# Wifi.net
KiCad netlist of a schematic drawn in Altium Designer
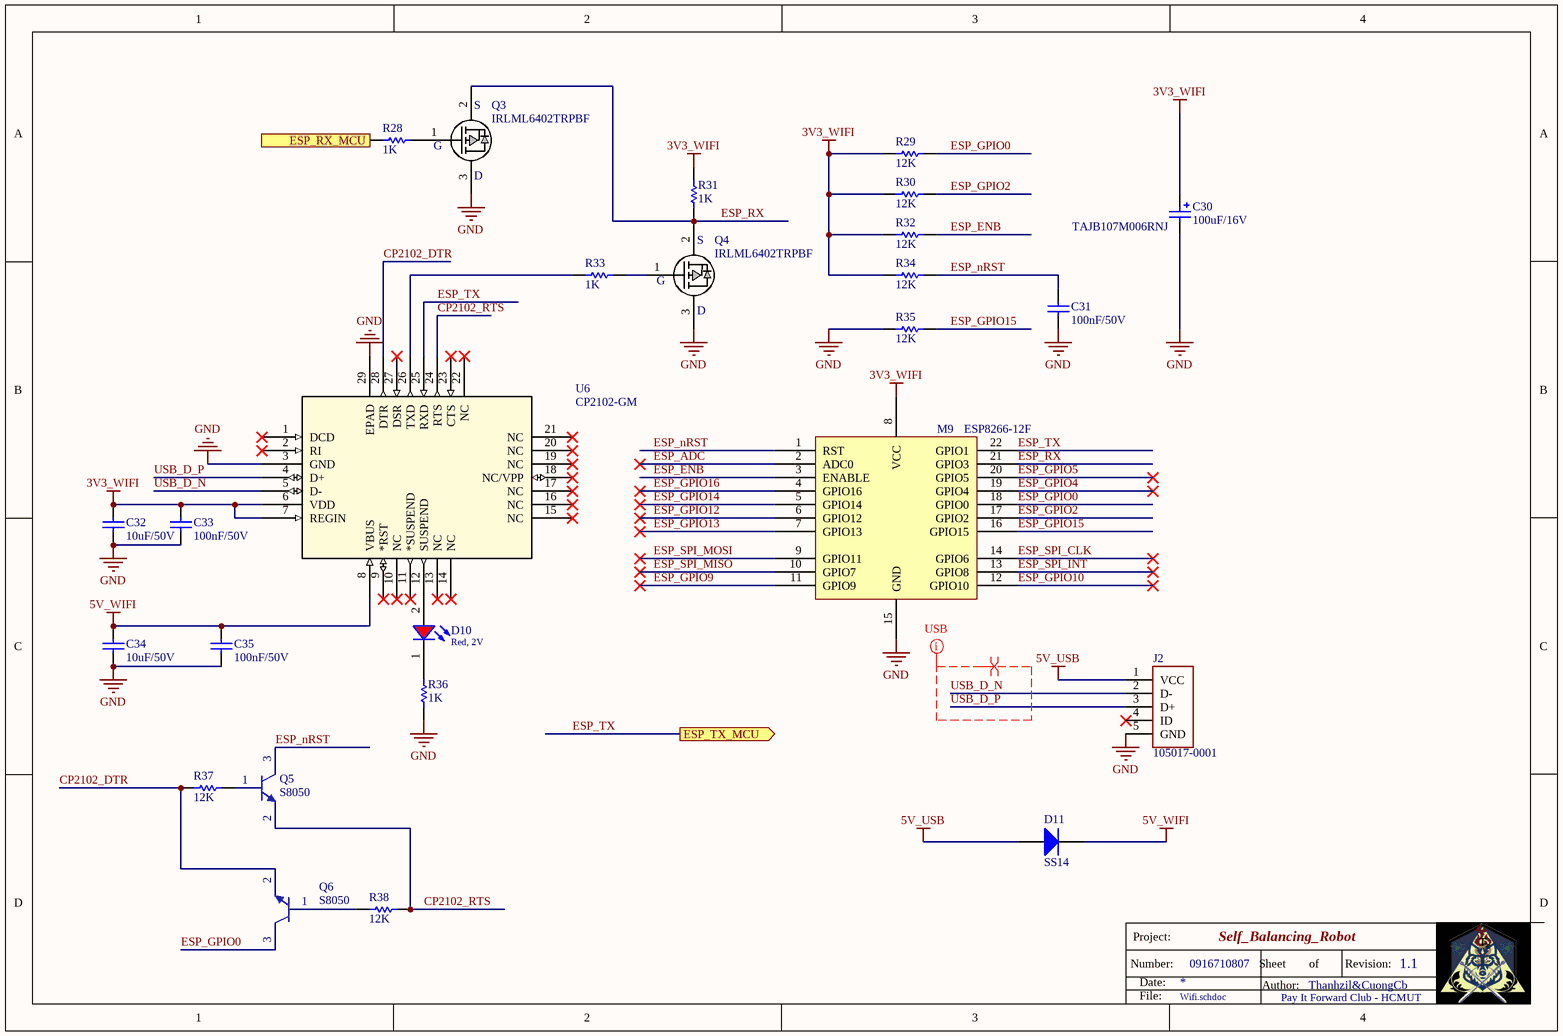
[diagram p0: Wifi.SchDoc]

(export (version "E")
  (design (tool "Eeschema 10.0.6"))
  (components
    (comp (ref "C30")
      (value "100uF/16V")
      (footprint "CAP_SM_TAN")
      (fields
        (field (name "MANUFACTURER") "Nichicon")
        (field (name "MANUFACTURER PART NUMBER") "UWX1C101MCL1GB")
        (field (name "Comment") "TAJB107M006RNJ")
      )
      (libsource (lib "Capacitor") (part "Cap-Tan-100uF-16V"))
    )
    (comp (ref "C31")
      (value "100nF/50V")
      (footprint "CAP-SM-0805")
      (description "CAP CER 0.1UF 50V Y5V 0805")
      (fields
        (field (name "MANUFACTURER") "Samsung Electro-Mechanics")
        (field (name "MANUFACTURER PART NUMBER") "CL21F104ZBCNNNC")
      )
      (libsource (lib "Capacitor") (part "Cap-100nF-50V-0805"))
    )
    (comp (ref "C32")
      (value "10uF/50V")
      (footprint "CAP-SM-0805")
      (description "CAP CER 10UF 50V X5R 0805")
      (fields
        (field (name "MANUFACTURER") "Yageo")
        (field (name "MANUFACTURER PART NUMBER") "CC0805KKX5R9BB106")
      )
      (libsource (lib "Capacitor") (part "Cap-10uF-50V-0805"))
    )
    (comp (ref "C33")
      (value "100nF/50V")
      (footprint "CAP-SM-0805")
      (description "CAP CER 0.1UF 50V Y5V 0805")
      (fields
        (field (name "MANUFACTURER") "Samsung Electro-Mechanics")
        (field (name "MANUFACTURER PART NUMBER") "CL21F104ZBCNNNC")
      )
      (libsource (lib "Capacitor") (part "Cap-100nF-50V-0805"))
    )
    (comp (ref "C34")
      (value "10uF/50V")
      (footprint "CAP-SM-0805")
      (description "CAP CER 10UF 50V X5R 0805")
      (fields
        (field (name "MANUFACTURER") "Yageo")
        (field (name "MANUFACTURER PART NUMBER") "CC0805KKX5R9BB106")
      )
      (libsource (lib "Capacitor") (part "Cap-10uF-50V-0805"))
    )
    (comp (ref "C35")
      (value "100nF/50V")
      (footprint "CAP-SM-0805")
      (description "CAP CER 0.1UF 50V Y5V 0805")
      (fields
        (field (name "MANUFACTURER") "Samsung Electro-Mechanics")
        (field (name "MANUFACTURER PART NUMBER") "CL21F104ZBCNNNC")
      )
      (libsource (lib "Capacitor") (part "Cap-100nF-50V-0805"))
    )
    (comp (ref "D10")
      (value "Red, 2V")
      (footprint "WL-SMCW_0805")
      (description "WL-SMCW SMT Mono-color Chip LED Waterclear, size 0805, Red, 2V, 140deg")
      (fields (field (name "PART NUMBER") "150080RS75000") (field (name "PUBLISHER") "Wurth Elektronik"))
      (libsource (lib "LED_150060BS75000_Altium_WL-SMCW_rev20a") (part "150080RS75000"))
    )
    (comp (ref "D11")
      (value "SS14")
      (footprint "SS14")
      (description "DIODE SCHOTTKY 40V 1A SMA")
      (fields (field (name "MANUFACTURER") "ON Semiconductor"))
      (libsource (lib "Diode") (part "Diode-SS14"))
    )
    (comp (ref "J2")
      (value "105017-0001")
      (footprint "CONN_105017-0001")
      (description "No Description Available")
      (fields (field (name "COPYRIGHT") "Copyright (C) 2018 Accelerated Designs. All rights reserved"))
      (libsource (lib "Header-connector") (part "105017-0001"))
    )
    (comp (ref "M9")
      (value "ESP8266-12F")
      (footprint "ESP8266-12F")
      (fields (field (name "LOCAL SUPPLIER LINK PART NUMBER") "HS000912"))
      (libsource (lib "PIFWRoBot") (part "ESP8266-12F"))
    )
    (comp (ref "Q3")
      (value "IRLML6402TRPBF")
      (footprint "SOT23_NEX")
      (description "P-Channel 20V 3.7A (Ta) 1.3W (Ta) Surface Mount Micro3™/SOT-23")
      (libsource (lib "MOSFET") (part "IRLML6402TRPBF"))
    )
    (comp (ref "Q4")
      (value "IRLML6402TRPBF")
      (footprint "SOT23_NEX")
      (description "P-Channel 20V 3.7A (Ta) 1.3W (Ta) Surface Mount Micro3™/SOT-23")
      (libsource (lib "MOSFET") (part "IRLML6402TRPBF"))
    )
    (comp (ref "Q5") (value "S8050") (footprint "SOT23_NEX") (libsource (lib "BJT") (part "S8050")))
    (comp (ref "Q6") (value "S8050") (footprint "SOT23_NEX") (libsource (lib "BJT") (part "S8050")))
    (comp (ref "R28")
      (value "1K")
      (footprint "Resistor:RES-SM-0805")
      (description "RES 1K OHM 1% 1/4W 0805")
      (fields
        (field (name "MANUFACTURER") "Stackpole Electronics Inc")
        (field (name "MANUFACTURER PART NUMBER") "RNCP0805FTD1K00")
      )
      (libsource (lib "Resistor") (part "Res-1K-0805"))
    )
    (comp (ref "R29")
      (value "12K")
      (footprint "Resistor:RES-SM-0805")
      (description "RES 12 KOHM JUMPER 0805")
      (fields
        (field (name "MANUFACTURER") "Vishay Thin Film")
        (field (name "MANUFACTURER PART NUMBER") "PAT0805E3121BST1")
      )
      (libsource (lib "Resistor") (part "Res-12K-0805"))
    )
    (comp (ref "R30")
      (value "12K")
      (footprint "Resistor:RES-SM-0805")
      (description "RES 12 KOHM JUMPER 0805")
      (fields
        (field (name "MANUFACTURER") "Vishay Thin Film")
        (field (name "MANUFACTURER PART NUMBER") "PAT0805E3121BST1")
      )
      (libsource (lib "Resistor") (part "Res-12K-0805"))
    )
    (comp (ref "R31")
      (value "1K")
      (footprint "Resistor:RES-SM-0805")
      (description "RES 1K OHM 1% 1/4W 0805")
      (fields
        (field (name "MANUFACTURER") "Stackpole Electronics Inc")
        (field (name "MANUFACTURER PART NUMBER") "RNCP0805FTD1K00")
      )
      (libsource (lib "Resistor") (part "Res-1K-0805"))
    )
    (comp (ref "R32")
      (value "12K")
      (footprint "Resistor:RES-SM-0805")
      (description "RES 12 KOHM JUMPER 0805")
      (fields
        (field (name "MANUFACTURER") "Vishay Thin Film")
        (field (name "MANUFACTURER PART NUMBER") "PAT0805E3121BST1")
      )
      (libsource (lib "Resistor") (part "Res-12K-0805"))
    )
    (comp (ref "R33")
      (value "1K")
      (footprint "Resistor:RES-SM-0805")
      (description "RES 1K OHM 1% 1/4W 0805")
      (fields
        (field (name "MANUFACTURER") "Stackpole Electronics Inc")
        (field (name "MANUFACTURER PART NUMBER") "RNCP0805FTD1K00")
      )
      (libsource (lib "Resistor") (part "Res-1K-0805"))
    )
    (comp (ref "R34")
      (value "12K")
      (footprint "Resistor:RES-SM-0805")
      (description "RES 12 KOHM JUMPER 0805")
      (fields
        (field (name "MANUFACTURER") "Vishay Thin Film")
        (field (name "MANUFACTURER PART NUMBER") "PAT0805E3121BST1")
      )
      (libsource (lib "Resistor") (part "Res-12K-0805"))
    )
    (comp (ref "R35")
      (value "12K")
      (footprint "Resistor:RES-SM-0805")
      (description "RES 12 KOHM JUMPER 0805")
      (fields
        (field (name "MANUFACTURER") "Vishay Thin Film")
        (field (name "MANUFACTURER PART NUMBER") "PAT0805E3121BST1")
      )
      (libsource (lib "Resistor") (part "Res-12K-0805"))
    )
    (comp (ref "R36")
      (value "1K")
      (footprint "Resistor:RES-SM-0805")
      (description "RES 1K OHM 1% 1/4W 0805")
      (fields
        (field (name "MANUFACTURER") "Stackpole Electronics Inc")
        (field (name "MANUFACTURER PART NUMBER") "RNCP0805FTD1K00")
      )
      (libsource (lib "Resistor") (part "Res-1K-0805"))
    )
    (comp (ref "R37")
      (value "12K")
      (footprint "Resistor:RES-SM-0805")
      (description "RES 12 KOHM JUMPER 0805")
      (fields
        (field (name "MANUFACTURER") "Vishay Thin Film")
        (field (name "MANUFACTURER PART NUMBER") "PAT0805E3121BST1")
      )
      (libsource (lib "Resistor") (part "Res-12K-0805"))
    )
    (comp (ref "R38")
      (value "12K")
      (footprint "Resistor:RES-SM-0805")
      (description "RES 12 KOHM JUMPER 0805")
      (fields
        (field (name "MANUFACTURER") "Vishay Thin Film")
        (field (name "MANUFACTURER PART NUMBER") "PAT0805E3121BST1")
      )
      (libsource (lib "Resistor") (part "Res-12K-0805"))
    )
    (comp (ref "U6")
      (value "CP2102-GM")
      (footprint "CP2102-GM")
      (fields (field (name "COPYRIGHT") "Copyright (C) 2018 Accelerated Designs. All rights reserved"))
      (libsource (lib "PIFWRoBot") (part "CP2102-GM"))
    )
  )
  (nets
    (net (code "1") (name "/CP2102_DTR") (class "Default")
      (node (ref "Q6") (pin "2") (pinfunction "E_2") (pintype "passive"))
      (node (ref "R37") (pin "1") (pinfunction "1_1") (pintype "passive"))
      (node (ref "U6") (pin "28") (pinfunction "DTR_28") (pintype "output"))
    )
    (net (code "2") (name "/CP2102_RTS") (class "Default")
      (node (ref "Q5") (pin "2") (pinfunction "E_2") (pintype "passive"))
      (node (ref "R38") (pin "2") (pinfunction "2_2") (pintype "passive"))
      (node (ref "U6") (pin "24") (pinfunction "RTS_24") (pintype "output"))
    )
    (net (code "3") (name "/ESP_ADC") (class "Default")
      (node (ref "M9") (pin "2") (pinfunction "ADC0_2") (pintype "passive+no_connect"))
    )
    (net (code "4") (name "/ESP_ENB") (class "Default")
      (node (ref "M9") (pin "3") (pinfunction "ENABLE_3") (pintype "passive"))
      (node (ref "R32") (pin "2") (pinfunction "2_2") (pintype "passive"))
    )
    (net (code "5") (name "/ESP_GPIO0") (class "Default")
      (node (ref "M9") (pin "18") (pinfunction "GPIO0_18") (pintype "passive"))
      (node (ref "Q6") (pin "3") (pinfunction "C_3") (pintype "passive"))
      (node (ref "R29") (pin "2") (pinfunction "2_2") (pintype "passive"))
    )
    (net (code "6") (name "/ESP_GPIO2") (class "Default")
      (node (ref "M9") (pin "17") (pinfunction "GPIO2_17") (pintype "passive"))
      (node (ref "R30") (pin "2") (pinfunction "2_2") (pintype "passive"))
    )
    (net (code "7") (name "/ESP_GPIO4") (class "Default")
      (node (ref "M9") (pin "19") (pinfunction "GPIO4_19") (pintype "passive+no_connect"))
    )
    (net (code "8") (name "/ESP_GPIO5") (class "Default")
      (node (ref "M9") (pin "20") (pinfunction "GPIO5_20") (pintype "passive+no_connect"))
    )
    (net (code "9") (name "/ESP_GPIO9") (class "Default")
      (node (ref "M9") (pin "11") (pinfunction "GPIO9_11") (pintype "passive+no_connect"))
    )
    (net (code "10") (name "/ESP_GPIO10") (class "Default")
      (node (ref "M9") (pin "12") (pinfunction "GPIO10_12") (pintype "passive+no_connect"))
    )
    (net (code "11") (name "/ESP_GPIO12") (class "Default")
      (node (ref "M9") (pin "6") (pinfunction "GPIO12_6") (pintype "passive+no_connect"))
    )
    (net (code "12") (name "/ESP_GPIO13") (class "Default")
      (node (ref "M9") (pin "7") (pinfunction "GPIO13_7") (pintype "passive+no_connect"))
    )
    (net (code "13") (name "/ESP_GPIO14") (class "Default")
      (node (ref "M9") (pin "5") (pinfunction "GPIO14_5") (pintype "passive+no_connect"))
    )
    (net (code "14") (name "/ESP_GPIO15") (class "Default")
      (node (ref "M9") (pin "16") (pinfunction "GPIO15_16") (pintype "passive"))
      (node (ref "R35") (pin "2") (pinfunction "2_2") (pintype "passive"))
    )
    (net (code "15") (name "/ESP_GPIO16") (class "Default")
      (node (ref "M9") (pin "4") (pinfunction "GPIO16_4") (pintype "passive+no_connect"))
    )
    (net (code "16") (name "/ESP_RX") (class "Default")
      (node (ref "M9") (pin "21") (pinfunction "GPIO3_21") (pintype "passive"))
      (node (ref "Q3") (pin "2") (pinfunction "S_2") (pintype "passive"))
      (node (ref "Q4") (pin "2") (pinfunction "S_2") (pintype "passive"))
      (node (ref "R31") (pin "1") (pinfunction "1_1") (pintype "passive"))
    )
    (net (code "17") (name "/ESP_RX_MCU") (class "Default")
      (node (ref "R28") (pin "1") (pinfunction "1_1") (pintype "passive"))
    )
    (net (code "18") (name "/ESP_SPI_CLK") (class "Default")
      (node (ref "M9") (pin "14") (pinfunction "GPIO6_14") (pintype "passive+no_connect"))
    )
    (net (code "19") (name "/ESP_SPI_INT") (class "Default")
      (node (ref "M9") (pin "13") (pinfunction "GPIO8_13") (pintype "passive+no_connect"))
    )
    (net (code "20") (name "/ESP_SPI_MISO") (class "Default")
      (node (ref "M9") (pin "10") (pinfunction "GPIO7_10") (pintype "passive+no_connect"))
    )
    (net (code "21") (name "/ESP_SPI_MOSI") (class "Default")
      (node (ref "M9") (pin "9") (pinfunction "GPIO11_9") (pintype "passive+no_connect"))
    )
    (net (code "22") (name "/ESP_TX") (class "Default")
      (node (ref "M9") (pin "22") (pinfunction "GPIO1_22") (pintype "passive"))
      (node (ref "U6") (pin "25") (pinfunction "RXD_25") (pintype "input"))
    )
    (net (code "23") (name "/ESP_nRST") (class "Default")
      (node (ref "C31") (pin "2") (pinfunction "2_2") (pintype "passive"))
      (node (ref "M9") (pin "1") (pinfunction "RST_1") (pintype "passive"))
      (node (ref "Q5") (pin "3") (pinfunction "C_3") (pintype "passive"))
      (node (ref "R34") (pin "2") (pinfunction "2_2") (pintype "passive"))
    )
    (net (code "24") (name "/USB_D_N") (class "Default")
      (node (ref "J2") (pin "2") (pinfunction "D-_2") (pintype "passive"))
      (node (ref "U6") (pin "5") (pinfunction "D-_5") (pintype "bidirectional"))
    )
    (net (code "25") (name "/USB_D_P") (class "Default")
      (node (ref "J2") (pin "3") (pinfunction "D+_3") (pintype "passive"))
      (node (ref "U6") (pin "4") (pinfunction "D+_4") (pintype "bidirectional"))
    )
    (net (code "26") (name "3V3_WIFI") (class "Default")
      (node (ref "C30") (pin "1") (pinfunction "1_1") (pintype "passive"))
      (node (ref "C32") (pin "1") (pinfunction "1_1") (pintype "passive"))
      (node (ref "C33") (pin "2") (pinfunction "2_2") (pintype "passive"))
      (node (ref "M9") (pin "8") (pinfunction "VCC_8") (pintype "passive"))
      (node (ref "R29") (pin "1") (pinfunction "1_1") (pintype "passive"))
      (node (ref "R30") (pin "1") (pinfunction "1_1") (pintype "passive"))
      (node (ref "R31") (pin "2") (pinfunction "2_2") (pintype "passive"))
      (node (ref "R32") (pin "1") (pinfunction "1_1") (pintype "passive"))
      (node (ref "R34") (pin "1") (pinfunction "1_1") (pintype "passive"))
      (node (ref "U6") (pin "6") (pinfunction "VDD_6") (pintype "power_in"))
      (node (ref "U6") (pin "7") (pinfunction "REGIN_7") (pintype "input"))
    )
    (net (code "27") (name "5V_USB") (class "Default")
      (node (ref "D11") (pin "2") (pinfunction "A_2") (pintype "passive"))
      (node (ref "J2") (pin "1") (pinfunction "VCC_1") (pintype "passive"))
    )
    (net (code "28") (name "5V_WIFI") (class "Default")
      (node (ref "C34") (pin "2") (pinfunction "2_2") (pintype "passive"))
      (node (ref "C35") (pin "2") (pinfunction "2_2") (pintype "passive"))
      (node (ref "D11") (pin "1") (pinfunction "K_1") (pintype "passive"))
      (node (ref "U6") (pin "8") (pinfunction "VBUS_8") (pintype "input"))
    )
    (net (code "29") (name "GND") (class "Default")
      (node (ref "C30") (pin "2") (pinfunction "2_2") (pintype "passive"))
      (node (ref "C31") (pin "1") (pinfunction "1_1") (pintype "passive"))
      (node (ref "C32") (pin "2") (pinfunction "2_2") (pintype "passive"))
      (node (ref "C33") (pin "1") (pinfunction "1_1") (pintype "passive"))
      (node (ref "C34") (pin "1") (pinfunction "1_1") (pintype "passive"))
      (node (ref "C35") (pin "1") (pinfunction "1_1") (pintype "passive"))
      (node (ref "J2") (pin "5") (pinfunction "GND_5") (pintype "passive"))
      (node (ref "M9") (pin "15") (pinfunction "GND_15") (pintype "passive"))
      (node (ref "Q3") (pin "3") (pinfunction "D_3") (pintype "passive"))
      (node (ref "Q4") (pin "3") (pinfunction "D_3") (pintype "passive"))
      (node (ref "R35") (pin "1") (pinfunction "1_1") (pintype "passive"))
      (node (ref "R36") (pin "1") (pinfunction "1_1") (pintype "passive"))
      (node (ref "U6") (pin "29") (pinfunction "EPAD_29") (pintype "passive"))
      (node (ref "U6") (pin "3") (pinfunction "GND_3") (pintype "power_in"))
    )
    (net (code "30") (name "Net-(D10-A)") (class "Default")
      (node (ref "D10") (pin "2") (pinfunction "A_2") (pintype "passive"))
      (node (ref "U6") (pin "12") (pinfunction "SUSPEND_12") (pintype "output"))
    )
    (net (code "31") (name "Net-(D10-K)") (class "Default")
      (node (ref "D10") (pin "1") (pinfunction "K_1") (pintype "passive"))
      (node (ref "R36") (pin "2") (pinfunction "2_2") (pintype "passive"))
    )
    (net (code "32") (name "Net-(Q3-G)") (class "Default")
      (node (ref "Q3") (pin "1") (pinfunction "G_1") (pintype "passive"))
      (node (ref "R28") (pin "2") (pinfunction "2_2") (pintype "passive"))
    )
    (net (code "33") (name "Net-(Q4-G)") (class "Default")
      (node (ref "Q4") (pin "1") (pinfunction "G_1") (pintype "passive"))
      (node (ref "R33") (pin "1") (pinfunction "1_1") (pintype "passive"))
    )
    (net (code "34") (name "Net-(Q5-B)") (class "Default")
      (node (ref "Q5") (pin "1") (pinfunction "B_1") (pintype "passive"))
      (node (ref "R37") (pin "2") (pinfunction "2_2") (pintype "passive"))
    )
    (net (code "35") (name "Net-(Q6-B)") (class "Default")
      (node (ref "Q6") (pin "1") (pinfunction "B_1") (pintype "passive"))
      (node (ref "R38") (pin "1") (pinfunction "1_1") (pintype "passive"))
    )
    (net (code "36") (name "Net-(U6-TXD)") (class "Default")
      (node (ref "R33") (pin "2") (pinfunction "2_2") (pintype "passive"))
      (node (ref "U6") (pin "26") (pinfunction "TXD_26") (pintype "output"))
    )
    (net (code "37") (name "unconnected-(J2-ID-Pad4)") (class "Default")
      (node (ref "J2") (pin "4") (pinfunction "ID_4") (pintype "passive+no_connect"))
    )
    (net (code "38") (name "unconnected-(U6-*RST-Pad9)") (class "Default")
      (node (ref "U6") (pin "9") (pinfunction "*RST_9") (pintype "bidirectional+no_connect"))
    )
    (net (code "39") (name "unconnected-(U6-*SUSPEND-Pad11)") (class "Default")
      (node (ref "U6") (pin "11") (pinfunction "*SUSPEND_11") (pintype "output+no_connect"))
    )
    (net (code "40") (name "unconnected-(U6-CTS-Pad23)") (class "Default")
      (node (ref "U6") (pin "23") (pinfunction "CTS_23") (pintype "input+no_connect"))
    )
    (net (code "41") (name "unconnected-(U6-DCD-Pad1)") (class "Default")
      (node (ref "U6") (pin "1") (pinfunction "DCD_1") (pintype "input+no_connect"))
    )
    (net (code "42") (name "unconnected-(U6-DSR-Pad27)") (class "Default")
      (node (ref "U6") (pin "27") (pinfunction "DSR_27") (pintype "input+no_connect"))
    )
    (net (code "43") (name "unconnected-(U6-NC-Pad10)") (class "Default")
      (node (ref "U6") (pin "10") (pinfunction "NC_10") (pintype "passive+no_connect"))
    )
    (net (code "44") (name "unconnected-(U6-NC-Pad13)") (class "Default")
      (node (ref "U6") (pin "13") (pinfunction "NC_13") (pintype "passive+no_connect"))
    )
    (net (code "45") (name "unconnected-(U6-NC-Pad14)") (class "Default")
      (node (ref "U6") (pin "14") (pinfunction "NC_14") (pintype "passive+no_connect"))
    )
    (net (code "46") (name "unconnected-(U6-NC-Pad15)") (class "Default")
      (node (ref "U6") (pin "15") (pinfunction "NC_15") (pintype "passive+no_connect"))
    )
    (net (code "47") (name "unconnected-(U6-NC-Pad16)") (class "Default")
      (node (ref "U6") (pin "16") (pinfunction "NC_16") (pintype "passive+no_connect"))
    )
    (net (code "48") (name "unconnected-(U6-NC-Pad17)") (class "Default")
      (node (ref "U6") (pin "17") (pinfunction "NC_17") (pintype "passive+no_connect"))
    )
    (net (code "49") (name "unconnected-(U6-NC-Pad19)") (class "Default")
      (node (ref "U6") (pin "19") (pinfunction "NC_19") (pintype "passive+no_connect"))
    )
    (net (code "50") (name "unconnected-(U6-NC-Pad20)") (class "Default")
      (node (ref "U6") (pin "20") (pinfunction "NC_20") (pintype "passive+no_connect"))
    )
    (net (code "51") (name "unconnected-(U6-NC-Pad21)") (class "Default")
      (node (ref "U6") (pin "21") (pinfunction "NC_21") (pintype "passive+no_connect"))
    )
    (net (code "52") (name "unconnected-(U6-NC-Pad22)") (class "Default")
      (node (ref "U6") (pin "22") (pinfunction "NC_22") (pintype "passive+no_connect"))
    )
    (net (code "53") (name "unconnected-(U6-NC{slash}VPP-Pad18)") (class "Default")
      (node (ref "U6") (pin "18") (pinfunction "NC/VPP_18") (pintype "bidirectional+no_connect"))
    )
    (net (code "54") (name "unconnected-(U6-RI-Pad2)") (class "Default")
      (node (ref "U6") (pin "2") (pinfunction "RI_2") (pintype "input+no_connect"))
    )
  )
)
